# Base_Arduino_clone.net
KiCad netlist of a schematic drawn in EAGLE
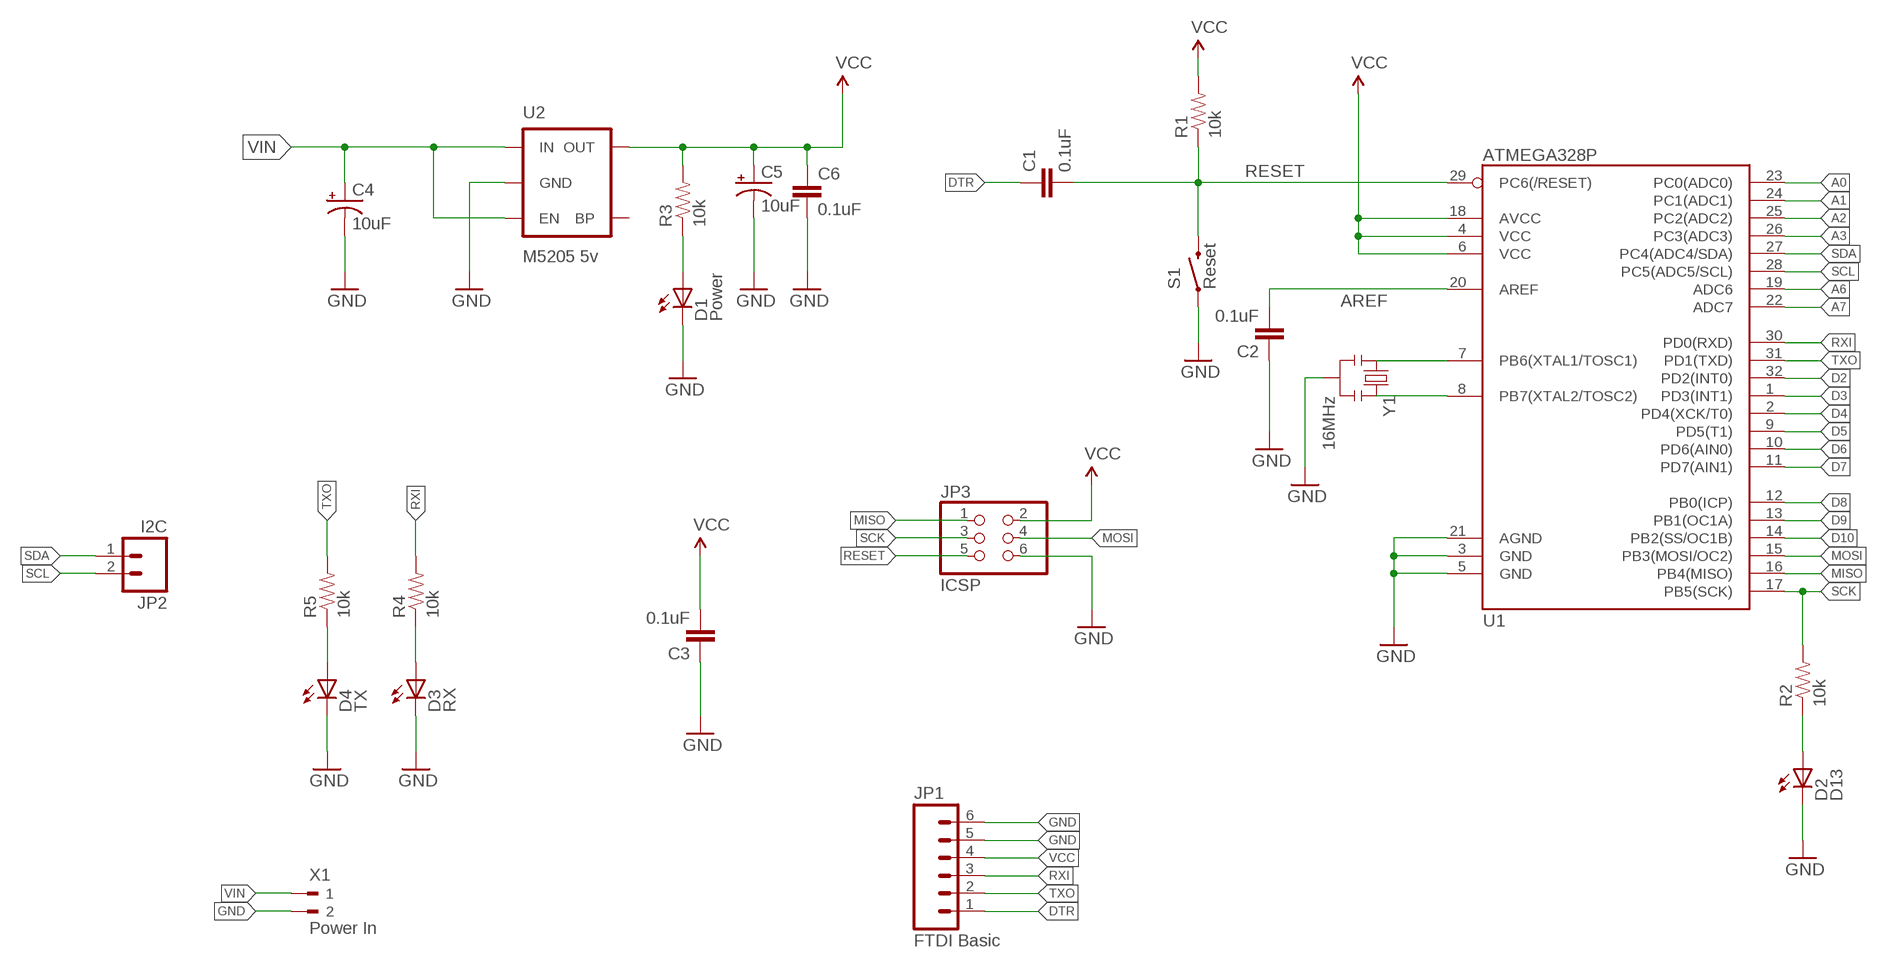
[diagram p0: schematic, sheet 1]

(export (version "E")
  (design (tool "Eeschema 10.0.6"))
  (components
    (comp (ref "C1")
      (value "0.1uF")
      (footprint "eagle-import:0603-CAP")
      (libsource (lib "eagle-import") (part "CAP0603-CAP"))
    )
    (comp (ref "C2")
      (value "0.1uF")
      (footprint "eagle-import:0603-CAP")
      (libsource (lib "eagle-import") (part "CAP0603-CAP"))
    )
    (comp (ref "C3")
      (value "0.1uF")
      (footprint "eagle-import:0603-CAP")
      (libsource (lib "eagle-import") (part "CAP0603-CAP"))
    )
    (comp (ref "C4")
      (value "10uF")
      (footprint "eagle-import:EIA3216")
      (libsource (lib "eagle-import") (part "CAP_POL1206"))
    )
    (comp (ref "C5")
      (value "10uF")
      (footprint "eagle-import:EIA3216")
      (libsource (lib "eagle-import") (part "CAP_POL1206"))
    )
    (comp (ref "C6")
      (value "0.1uF")
      (footprint "eagle-import:0603-CAP")
      (libsource (lib "eagle-import") (part "CAP0603-CAP"))
    )
    (comp (ref "D1")
      (value "Power")
      (footprint "eagle-import:LED-0603")
      (libsource (lib "eagle-import") (part "LED-RED0603"))
    )
    (comp (ref "D2")
      (value "D13")
      (footprint "eagle-import:LED-0603")
      (libsource (lib "eagle-import") (part "LED-RED0603"))
    )
    (comp (ref "D3")
      (value "RX")
      (footprint "eagle-import:LED-0603")
      (libsource (lib "eagle-import") (part "LED-GREEN0603"))
    )
    (comp (ref "D4")
      (value "TX")
      (footprint "eagle-import:LED-0603")
      (libsource (lib "eagle-import") (part "LED-RED0603"))
    )
    (comp (ref "JP1")
      (value "FTDI Basic")
      (footprint "eagle-import:1X06")
      (libsource (lib "eagle-import") (part "M06SIP"))
    )
    (comp (ref "JP2")
      (value "I2C")
      (footprint "eagle-import:1X02")
      (libsource (lib "eagle-import") (part "M02PTH"))
    )
    (comp (ref "JP3")
      (value "ICSP")
      (footprint "eagle-import:2X03")
      (libsource (lib "eagle-import") (part "PINHD-2X3"))
    )
    (comp (ref "R1")
      (value "10k")
      (footprint "eagle-import:0603-RES")
      (libsource (lib "eagle-import") (part "RESISTOR0603-RES"))
    )
    (comp (ref "R2")
      (value "10k")
      (footprint "eagle-import:0603-RES")
      (libsource (lib "eagle-import") (part "RESISTOR0603-RES"))
    )
    (comp (ref "R3")
      (value "10k")
      (footprint "eagle-import:0603-RES")
      (libsource (lib "eagle-import") (part "RESISTOR0603-RES"))
    )
    (comp (ref "R4")
      (value "10k")
      (footprint "eagle-import:0603-RES")
      (libsource (lib "eagle-import") (part "RESISTOR0603-RES"))
    )
    (comp (ref "R5")
      (value "10k")
      (footprint "eagle-import:0603-RES")
      (libsource (lib "eagle-import") (part "RESISTOR0603-RES"))
    )
    (comp (ref "S1")
      (value "Reset")
      (footprint "eagle-import:TACTILE_SWITCH_SMD")
      (libsource (lib "eagle-import") (part "SWITCH-MOMENTARY-2SMD"))
    )
    (comp (ref "U1")
      (value "ATMEGA328P")
      (footprint "eagle-import:TQFP32-08")
      (libsource (lib "eagle-import") (part "ATMEGA328_SMT"))
    )
    (comp (ref "U2")
      (value "M5205 5v")
      (footprint "eagle-import:SOT23-5")
      (libsource (lib "eagle-import") (part "MIC52055V"))
    )
    (comp (ref "X1")
      (value "Power In")
      (footprint "eagle-import:180G-2")
      (libsource (lib "eagle-import") (part "180G-2"))
    )
    (comp (ref "Y1")
      (value "16MHz")
      (footprint "eagle-import:RESONATOR-SMD")
      (libsource (lib "eagle-import") (part "RESONATOR16MHZ"))
    )
  )
  (nets
    (net (code "1") (name "/AREF") (class "Default")
      (node (ref "C2") (pin "2") (pinfunction "2_2") (pintype "passive"))
      (node (ref "U1") (pin "20") (pinfunction "AREF_20") (pintype "bidirectional"))
    )
    (net (code "2") (name "A0") (class "Default")
      (node (ref "U1") (pin "23") (pinfunction "PC0(ADC0)_23") (pintype "bidirectional"))
    )
    (net (code "3") (name "A1") (class "Default")
      (node (ref "U1") (pin "24") (pinfunction "PC1(ADC1)_24") (pintype "bidirectional"))
    )
    (net (code "4") (name "A2") (class "Default")
      (node (ref "U1") (pin "25") (pinfunction "PC2(ADC2)_25") (pintype "bidirectional"))
    )
    (net (code "5") (name "A3") (class "Default")
      (node (ref "U1") (pin "26") (pinfunction "PC3(ADC3)_26") (pintype "bidirectional"))
    )
    (net (code "6") (name "A6") (class "Default")
      (node (ref "U1") (pin "19") (pinfunction "ADC6_19") (pintype "bidirectional"))
    )
    (net (code "7") (name "A7") (class "Default")
      (node (ref "U1") (pin "22") (pinfunction "ADC7_22") (pintype "bidirectional"))
    )
    (net (code "8") (name "D2") (class "Default")
      (node (ref "U1") (pin "32") (pinfunction "PD2(INT0)_32") (pintype "bidirectional"))
    )
    (net (code "9") (name "D3") (class "Default")
      (node (ref "U1") (pin "1") (pinfunction "PD3(INT1)_1") (pintype "bidirectional"))
    )
    (net (code "10") (name "D4") (class "Default")
      (node (ref "U1") (pin "2") (pinfunction "PD4(XCK/T0)_2") (pintype "bidirectional"))
    )
    (net (code "11") (name "D5") (class "Default")
      (node (ref "U1") (pin "9") (pinfunction "PD5(T1)_9") (pintype "bidirectional"))
    )
    (net (code "12") (name "D6") (class "Default")
      (node (ref "U1") (pin "10") (pinfunction "PD6(AIN0)_10") (pintype "bidirectional"))
    )
    (net (code "13") (name "D7") (class "Default")
      (node (ref "U1") (pin "11") (pinfunction "PD7(AIN1)_11") (pintype "bidirectional"))
    )
    (net (code "14") (name "D8") (class "Default")
      (node (ref "U1") (pin "12") (pinfunction "PB0(ICP)_12") (pintype "bidirectional"))
    )
    (net (code "15") (name "D9") (class "Default")
      (node (ref "U1") (pin "13") (pinfunction "PB1(OC1A)_13") (pintype "bidirectional"))
    )
    (net (code "16") (name "D10") (class "Default")
      (node (ref "U1") (pin "14") (pinfunction "PB2(SS/OC1B)_14") (pintype "bidirectional"))
    )
    (net (code "17") (name "DTR") (class "Default")
      (node (ref "C1") (pin "1") (pinfunction "1_1") (pintype "passive"))
      (node (ref "JP1") (pin "1") (pinfunction "1_1") (pintype "passive"))
    )
    (net (code "18") (name "GND") (class "Default")
      (node (ref "C2") (pin "1") (pinfunction "1_1") (pintype "passive"))
      (node (ref "C3") (pin "1") (pinfunction "1_1") (pintype "passive"))
      (node (ref "C4") (pin "C") (pinfunction "-_C") (pintype "passive"))
      (node (ref "C5") (pin "C") (pinfunction "-_C") (pintype "passive"))
      (node (ref "C6") (pin "2") (pinfunction "2_2") (pintype "passive"))
      (node (ref "D1") (pin "C") (pinfunction "C_C") (pintype "passive"))
      (node (ref "D2") (pin "C") (pinfunction "C_C") (pintype "passive"))
      (node (ref "D3") (pin "C") (pinfunction "C_C") (pintype "passive"))
      (node (ref "D4") (pin "C") (pinfunction "C_C") (pintype "passive"))
      (node (ref "JP1") (pin "5") (pinfunction "5_5") (pintype "passive"))
      (node (ref "JP1") (pin "6") (pinfunction "6_6") (pintype "passive"))
      (node (ref "JP3") (pin "6") (pinfunction "6_6") (pintype "passive"))
      (node (ref "S1") (pin "1") (pinfunction "1_1") (pintype "passive"))
      (node (ref "U1") (pin "21") (pinfunction "AGND_21") (pintype "bidirectional"))
      (node (ref "U1") (pin "3") (pinfunction "GND_3") (pintype "bidirectional"))
      (node (ref "U1") (pin "5") (pinfunction "GND_5") (pintype "bidirectional"))
      (node (ref "U2") (pin "2") (pinfunction "GND_2") (pintype "input"))
      (node (ref "X1") (pin "2") (pinfunction "2_2") (pintype "passive"))
      (node (ref "Y1") (pin "2") (pinfunction "2_2") (pintype "passive"))
    )
    (net (code "19") (name "MISO") (class "Default")
      (node (ref "JP3") (pin "1") (pinfunction "1_1") (pintype "passive"))
      (node (ref "U1") (pin "16") (pinfunction "PB4(MISO)_16") (pintype "bidirectional"))
    )
    (net (code "20") (name "MOSI") (class "Default")
      (node (ref "JP3") (pin "4") (pinfunction "4_4") (pintype "passive"))
      (node (ref "U1") (pin "15") (pinfunction "PB3(MOSI/OC2)_15") (pintype "bidirectional"))
    )
    (net (code "21") (name "Net-(D1-PadA)") (class "Default")
      (node (ref "D1") (pin "A") (pinfunction "A_A") (pintype "passive"))
      (node (ref "R3") (pin "1") (pinfunction "1_1") (pintype "passive"))
    )
    (net (code "22") (name "Net-(D2-PadA)") (class "Default")
      (node (ref "D2") (pin "A") (pinfunction "A_A") (pintype "passive"))
      (node (ref "R2") (pin "1") (pinfunction "1_1") (pintype "passive"))
    )
    (net (code "23") (name "Net-(D3-PadA)") (class "Default")
      (node (ref "D3") (pin "A") (pinfunction "A_A") (pintype "passive"))
      (node (ref "R4") (pin "1") (pinfunction "1_1") (pintype "passive"))
    )
    (net (code "24") (name "Net-(D4-PadA)") (class "Default")
      (node (ref "D4") (pin "A") (pinfunction "A_A") (pintype "passive"))
      (node (ref "R5") (pin "1") (pinfunction "1_1") (pintype "passive"))
    )
    (net (code "25") (name "Net-(U1-PB6(XTAL1{slash}TOSC1))") (class "Default")
      (node (ref "U1") (pin "7") (pinfunction "PB6(XTAL1/TOSC1)_7") (pintype "bidirectional"))
      (node (ref "Y1") (pin "1") (pinfunction "1_1") (pintype "passive"))
    )
    (net (code "26") (name "Net-(U1-PB7(XTAL2{slash}TOSC2))") (class "Default")
      (node (ref "U1") (pin "8") (pinfunction "PB7(XTAL2/TOSC2)_8") (pintype "bidirectional"))
      (node (ref "Y1") (pin "3") (pinfunction "3_3") (pintype "passive"))
    )
    (net (code "27") (name "RESET") (class "Default")
      (node (ref "C1") (pin "2") (pinfunction "2_2") (pintype "passive"))
      (node (ref "JP3") (pin "5") (pinfunction "5_5") (pintype "passive"))
      (node (ref "R1") (pin "1") (pinfunction "1_1") (pintype "passive"))
      (node (ref "S1") (pin "3") (pinfunction "2_3") (pintype "passive"))
      (node (ref "U1") (pin "29") (pinfunction "PC6(/RESET)_29") (pintype "bidirectional"))
    )
    (net (code "28") (name "RXI") (class "Default")
      (node (ref "JP1") (pin "3") (pinfunction "3_3") (pintype "passive"))
      (node (ref "R4") (pin "2") (pinfunction "2_2") (pintype "passive"))
      (node (ref "U1") (pin "30") (pinfunction "PD0(RXD)_30") (pintype "bidirectional"))
    )
    (net (code "29") (name "SCK") (class "Default")
      (node (ref "JP3") (pin "3") (pinfunction "3_3") (pintype "passive"))
      (node (ref "R2") (pin "2") (pinfunction "2_2") (pintype "passive"))
      (node (ref "U1") (pin "17") (pinfunction "PB5(SCK)_17") (pintype "bidirectional"))
    )
    (net (code "30") (name "SCL") (class "Default")
      (node (ref "JP2") (pin "2") (pinfunction "2_2") (pintype "passive"))
      (node (ref "U1") (pin "28") (pinfunction "PC5(ADC5/SCL)_28") (pintype "bidirectional"))
    )
    (net (code "31") (name "SDA") (class "Default")
      (node (ref "JP2") (pin "1") (pinfunction "1_1") (pintype "passive"))
      (node (ref "U1") (pin "27") (pinfunction "PC4(ADC4/SDA)_27") (pintype "bidirectional"))
    )
    (net (code "32") (name "TXO") (class "Default")
      (node (ref "JP1") (pin "2") (pinfunction "2_2") (pintype "passive"))
      (node (ref "R5") (pin "2") (pinfunction "2_2") (pintype "passive"))
      (node (ref "U1") (pin "31") (pinfunction "PD1(TXD)_31") (pintype "bidirectional"))
    )
    (net (code "33") (name "VCC") (class "Default")
      (node (ref "C3") (pin "2") (pinfunction "2_2") (pintype "passive"))
      (node (ref "C5") (pin "A") (pinfunction "+_A") (pintype "passive"))
      (node (ref "C6") (pin "1") (pinfunction "1_1") (pintype "passive"))
      (node (ref "JP1") (pin "4") (pinfunction "4_4") (pintype "passive"))
      (node (ref "JP3") (pin "2") (pinfunction "2_2") (pintype "passive"))
      (node (ref "R1") (pin "2") (pinfunction "2_2") (pintype "passive"))
      (node (ref "R3") (pin "2") (pinfunction "2_2") (pintype "passive"))
      (node (ref "U1") (pin "18") (pinfunction "AVCC_18") (pintype "bidirectional"))
      (node (ref "U1") (pin "4") (pinfunction "VCC_4") (pintype "bidirectional"))
      (node (ref "U1") (pin "6") (pinfunction "VCC_6") (pintype "bidirectional"))
      (node (ref "U2") (pin "5") (pinfunction "OUT_5") (pintype "passive"))
    )
    (net (code "34") (name "VIN") (class "Default")
      (node (ref "C4") (pin "A") (pinfunction "+_A") (pintype "passive"))
      (node (ref "U2") (pin "1") (pinfunction "IN_1") (pintype "input"))
      (node (ref "U2") (pin "3") (pinfunction "EN_3") (pintype "input"))
      (node (ref "X1") (pin "1") (pinfunction "1_1") (pintype "passive"))
    )
    (net (code "35") (name "unconnected-(U2-BP-Pad4)") (class "Default")
      (node (ref "U2") (pin "4") (pinfunction "BP_4") (pintype "input"))
    )
  )
)
